# CCR.net
KiCad netlist of a schematic drawn in EAGLE
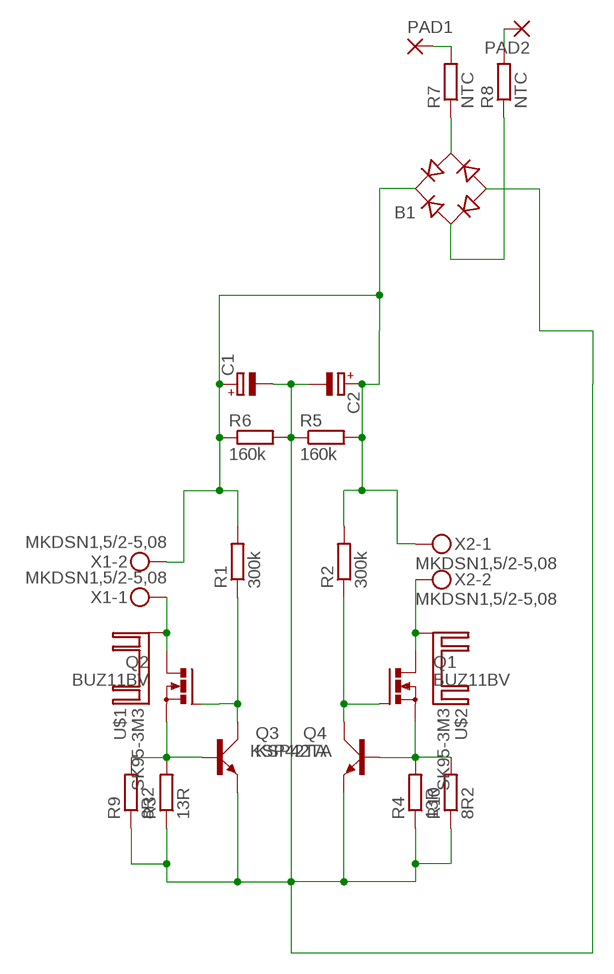
[diagram p0: schematic, sheet 1]

(export (version "E")
  (design (tool "Eeschema 10.0.6"))
  (components
    (comp (ref "B1")
      (value "RB1A")
      (footprint "eagle-import:RB1A")
      (libsource (lib "eagle-import") (part "RB1A"))
    )
    (comp (ref "C1")
      (value "CPOL-EUE7.5-18")
      (footprint "eagle-import:E7,5-18")
      (libsource (lib "eagle-import") (part "CPOL-EUE7.5-18"))
    )
    (comp (ref "C2")
      (value "CPOL-EUE7.5-18")
      (footprint "eagle-import:E7,5-18")
      (libsource (lib "eagle-import") (part "CPOL-EUE7.5-18"))
    )
    (comp (ref "PAD1")
      (value "3,81/1,4")
      (footprint "eagle-import:3,81_1,4")
      (libsource (lib "eagle-import") (part "3,81/1,4"))
    )
    (comp (ref "PAD2")
      (value "3,81/1,4")
      (footprint "eagle-import:3,81_1,4")
      (libsource (lib "eagle-import") (part "3,81/1,4"))
    )
    (comp (ref "Q1")
      (value "BUZ11BV")
      (footprint "eagle-import:TO220BV")
      (libsource (lib "eagle-import") (part "BUZ11BV"))
    )
    (comp (ref "Q2")
      (value "BUZ11BV")
      (footprint "eagle-import:TO220BV")
      (libsource (lib "eagle-import") (part "BUZ11BV"))
    )
    (comp (ref "Q3")
      (value "KSP42TA")
      (footprint "eagle-import:SOT-92WIDE")
      (libsource (lib "eagle-import") (part "KSP42TA"))
    )
    (comp (ref "Q4")
      (value "KSP42TA")
      (footprint "eagle-import:SOT-92WIDE")
      (libsource (lib "eagle-import") (part "KSP42TA"))
    )
    (comp (ref "R1")
      (value "300k")
      (footprint "eagle-import:0411_12")
      (libsource (lib "eagle-import") (part "R-EU_0411/12"))
    )
    (comp (ref "R2")
      (value "300k")
      (footprint "eagle-import:0411_12")
      (libsource (lib "eagle-import") (part "R-EU_0411/12"))
    )
    (comp (ref "R3")
      (value "13R")
      (footprint "eagle-import:0411_12")
      (libsource (lib "eagle-import") (part "R-EU_0411/12"))
    )
    (comp (ref "R4")
      (value "13R")
      (footprint "eagle-import:0411_12")
      (libsource (lib "eagle-import") (part "R-EU_0411/12"))
    )
    (comp (ref "R5")
      (value "160k")
      (footprint "eagle-import:0207_10")
      (libsource (lib "eagle-import") (part "R-EU_0207/10"))
    )
    (comp (ref "R6")
      (value "160k")
      (footprint "eagle-import:0207_10")
      (libsource (lib "eagle-import") (part "R-EU_0207/10"))
    )
    (comp (ref "R7")
      (value "NTC")
      (footprint "eagle-import:0207_10")
      (libsource (lib "eagle-import") (part "R-EU_0207/10"))
    )
    (comp (ref "R8")
      (value "NTC")
      (footprint "eagle-import:0207_10")
      (libsource (lib "eagle-import") (part "R-EU_0207/10"))
    )
    (comp (ref "R9")
      (value "8R2")
      (footprint "eagle-import:0411_12")
      (libsource (lib "eagle-import") (part "R-EU_0411/12"))
    )
    (comp (ref "R10")
      (value "8R2")
      (footprint "eagle-import:0411_12")
      (libsource (lib "eagle-import") (part "R-EU_0411/12"))
    )
    (comp (ref "U$1")
      (value "SK95-3M3")
      (footprint "eagle-import:SK95-3M3")
      (libsource (lib "eagle-import") (part "SK95-3M3"))
    )
    (comp (ref "U$2")
      (value "SK95-3M3")
      (footprint "eagle-import:SK95-3M3")
      (libsource (lib "eagle-import") (part "SK95-3M3"))
    )
    (comp (ref "X1")
      (value "MKDSN1,5/2-5,08")
      (footprint "eagle-import:MKDSN1,5_2-5,08")
      (libsource (lib "eagle-import") (part "MKDSN1,5/2-5,08"))
    )
    (comp (ref "X2")
      (value "MKDSN1,5/2-5,08")
      (footprint "eagle-import:MKDSN1,5_2-5,08")
      (libsource (lib "eagle-import") (part "MKDSN1,5/2-5,08"))
    )
  )
  (nets
    (net (code "1") (name "Net-(B1-Pad-)") (class "Default")
      (node (ref "B1") (pin "-") (pinfunction "-_-") (pintype "passive"))
      (node (ref "C1") (pin "-") (pinfunction "-_-") (pintype "passive"))
      (node (ref "C2") (pin "-") (pinfunction "-_-") (pintype "passive"))
      (node (ref "Q3") (pin "E") (pinfunction "E_E") (pintype "passive"))
      (node (ref "Q4") (pin "E") (pinfunction "E_E") (pintype "passive"))
      (node (ref "R10") (pin "1") (pinfunction "1_1") (pintype "passive"))
      (node (ref "R3") (pin "1") (pinfunction "1_1") (pintype "passive"))
      (node (ref "R4") (pin "1") (pinfunction "1_1") (pintype "passive"))
      (node (ref "R5") (pin "1") (pinfunction "1_1") (pintype "passive"))
      (node (ref "R6") (pin "2") (pinfunction "2_2") (pintype "passive"))
      (node (ref "R9") (pin "1") (pinfunction "1_1") (pintype "passive"))
    )
    (net (code "2") (name "Net-(B1-PadAC1)") (class "Default")
      (node (ref "B1") (pin "AC1") (pinfunction "AC1_AC1") (pintype "passive"))
      (node (ref "R8") (pin "1") (pinfunction "1_1") (pintype "passive"))
    )
    (net (code "3") (name "Net-(B1-PadAC2)") (class "Default")
      (node (ref "B1") (pin "AC2") (pinfunction "AC2_AC2") (pintype "passive"))
      (node (ref "R7") (pin "1") (pinfunction "1_1") (pintype "passive"))
    )
    (net (code "4") (name "Net-(PAD1-P)") (class "Default")
      (node (ref "PAD1") (pin "1") (pinfunction "P_1") (pintype "passive"))
      (node (ref "R7") (pin "2") (pinfunction "2_2") (pintype "passive"))
    )
    (net (code "5") (name "Net-(PAD2-P)") (class "Default")
      (node (ref "PAD2") (pin "1") (pinfunction "P_1") (pintype "passive"))
      (node (ref "R8") (pin "2") (pinfunction "2_2") (pintype "passive"))
    )
    (net (code "6") (name "Net-(Q1-PadG)") (class "Default")
      (node (ref "Q1") (pin "G") (pinfunction "G_G") (pintype "passive"))
      (node (ref "Q4") (pin "C") (pinfunction "C_C") (pintype "passive"))
      (node (ref "R2") (pin "1") (pinfunction "1_1") (pintype "passive"))
    )
    (net (code "7") (name "Net-(Q1-PadS)") (class "Default")
      (node (ref "Q1") (pin "S") (pinfunction "S_S") (pintype "passive"))
      (node (ref "Q4") (pin "B") (pinfunction "B_B") (pintype "passive"))
      (node (ref "R10") (pin "2") (pinfunction "2_2") (pintype "passive"))
      (node (ref "R4") (pin "2") (pinfunction "2_2") (pintype "passive"))
    )
    (net (code "8") (name "Net-(Q2-PadG)") (class "Default")
      (node (ref "Q2") (pin "G") (pinfunction "G_G") (pintype "passive"))
      (node (ref "Q3") (pin "C") (pinfunction "C_C") (pintype "passive"))
      (node (ref "R1") (pin "1") (pinfunction "1_1") (pintype "passive"))
    )
    (net (code "9") (name "Net-(Q2-PadS)") (class "Default")
      (node (ref "Q2") (pin "S") (pinfunction "S_S") (pintype "passive"))
      (node (ref "Q3") (pin "B") (pinfunction "B_B") (pintype "passive"))
      (node (ref "R3") (pin "2") (pinfunction "2_2") (pintype "passive"))
      (node (ref "R9") (pin "2") (pinfunction "2_2") (pintype "passive"))
    )
    (net (code "10") (name "Net-(U$1-K)") (class "Default")
      (node (ref "Q2") (pin "D") (pinfunction "D_D") (pintype "passive"))
      (node (ref "U$1") (pin "P$1") (pinfunction "K_P$1") (pintype "passive"))
      (node (ref "X1") (pin "1") (pinfunction "KL_1") (pintype "passive"))
    )
    (net (code "11") (name "Net-(U$2-K)") (class "Default")
      (node (ref "Q1") (pin "D") (pinfunction "D_D") (pintype "passive"))
      (node (ref "U$2") (pin "P$1") (pinfunction "K_P$1") (pintype "passive"))
      (node (ref "X2") (pin "2") (pinfunction "KL_2") (pintype "passive"))
    )
    (net (code "12") (name "Net-(X1B-KL)") (class "Default")
      (node (ref "B1") (pin "+") (pinfunction "+_+") (pintype "passive"))
      (node (ref "C1") (pin "+") (pinfunction "+_+") (pintype "passive"))
      (node (ref "C2") (pin "+") (pinfunction "+_+") (pintype "passive"))
      (node (ref "R1") (pin "2") (pinfunction "2_2") (pintype "passive"))
      (node (ref "R2") (pin "2") (pinfunction "2_2") (pintype "passive"))
      (node (ref "R5") (pin "2") (pinfunction "2_2") (pintype "passive"))
      (node (ref "R6") (pin "1") (pinfunction "1_1") (pintype "passive"))
      (node (ref "X1") (pin "2") (pinfunction "KL_2") (pintype "passive"))
      (node (ref "X2") (pin "1") (pinfunction "KL_1") (pintype "passive"))
    )
  )
)
